# CruiseControlSystemElectricalSchematic_1.net
KiCad netlist of a schematic drawn in EasyEDA
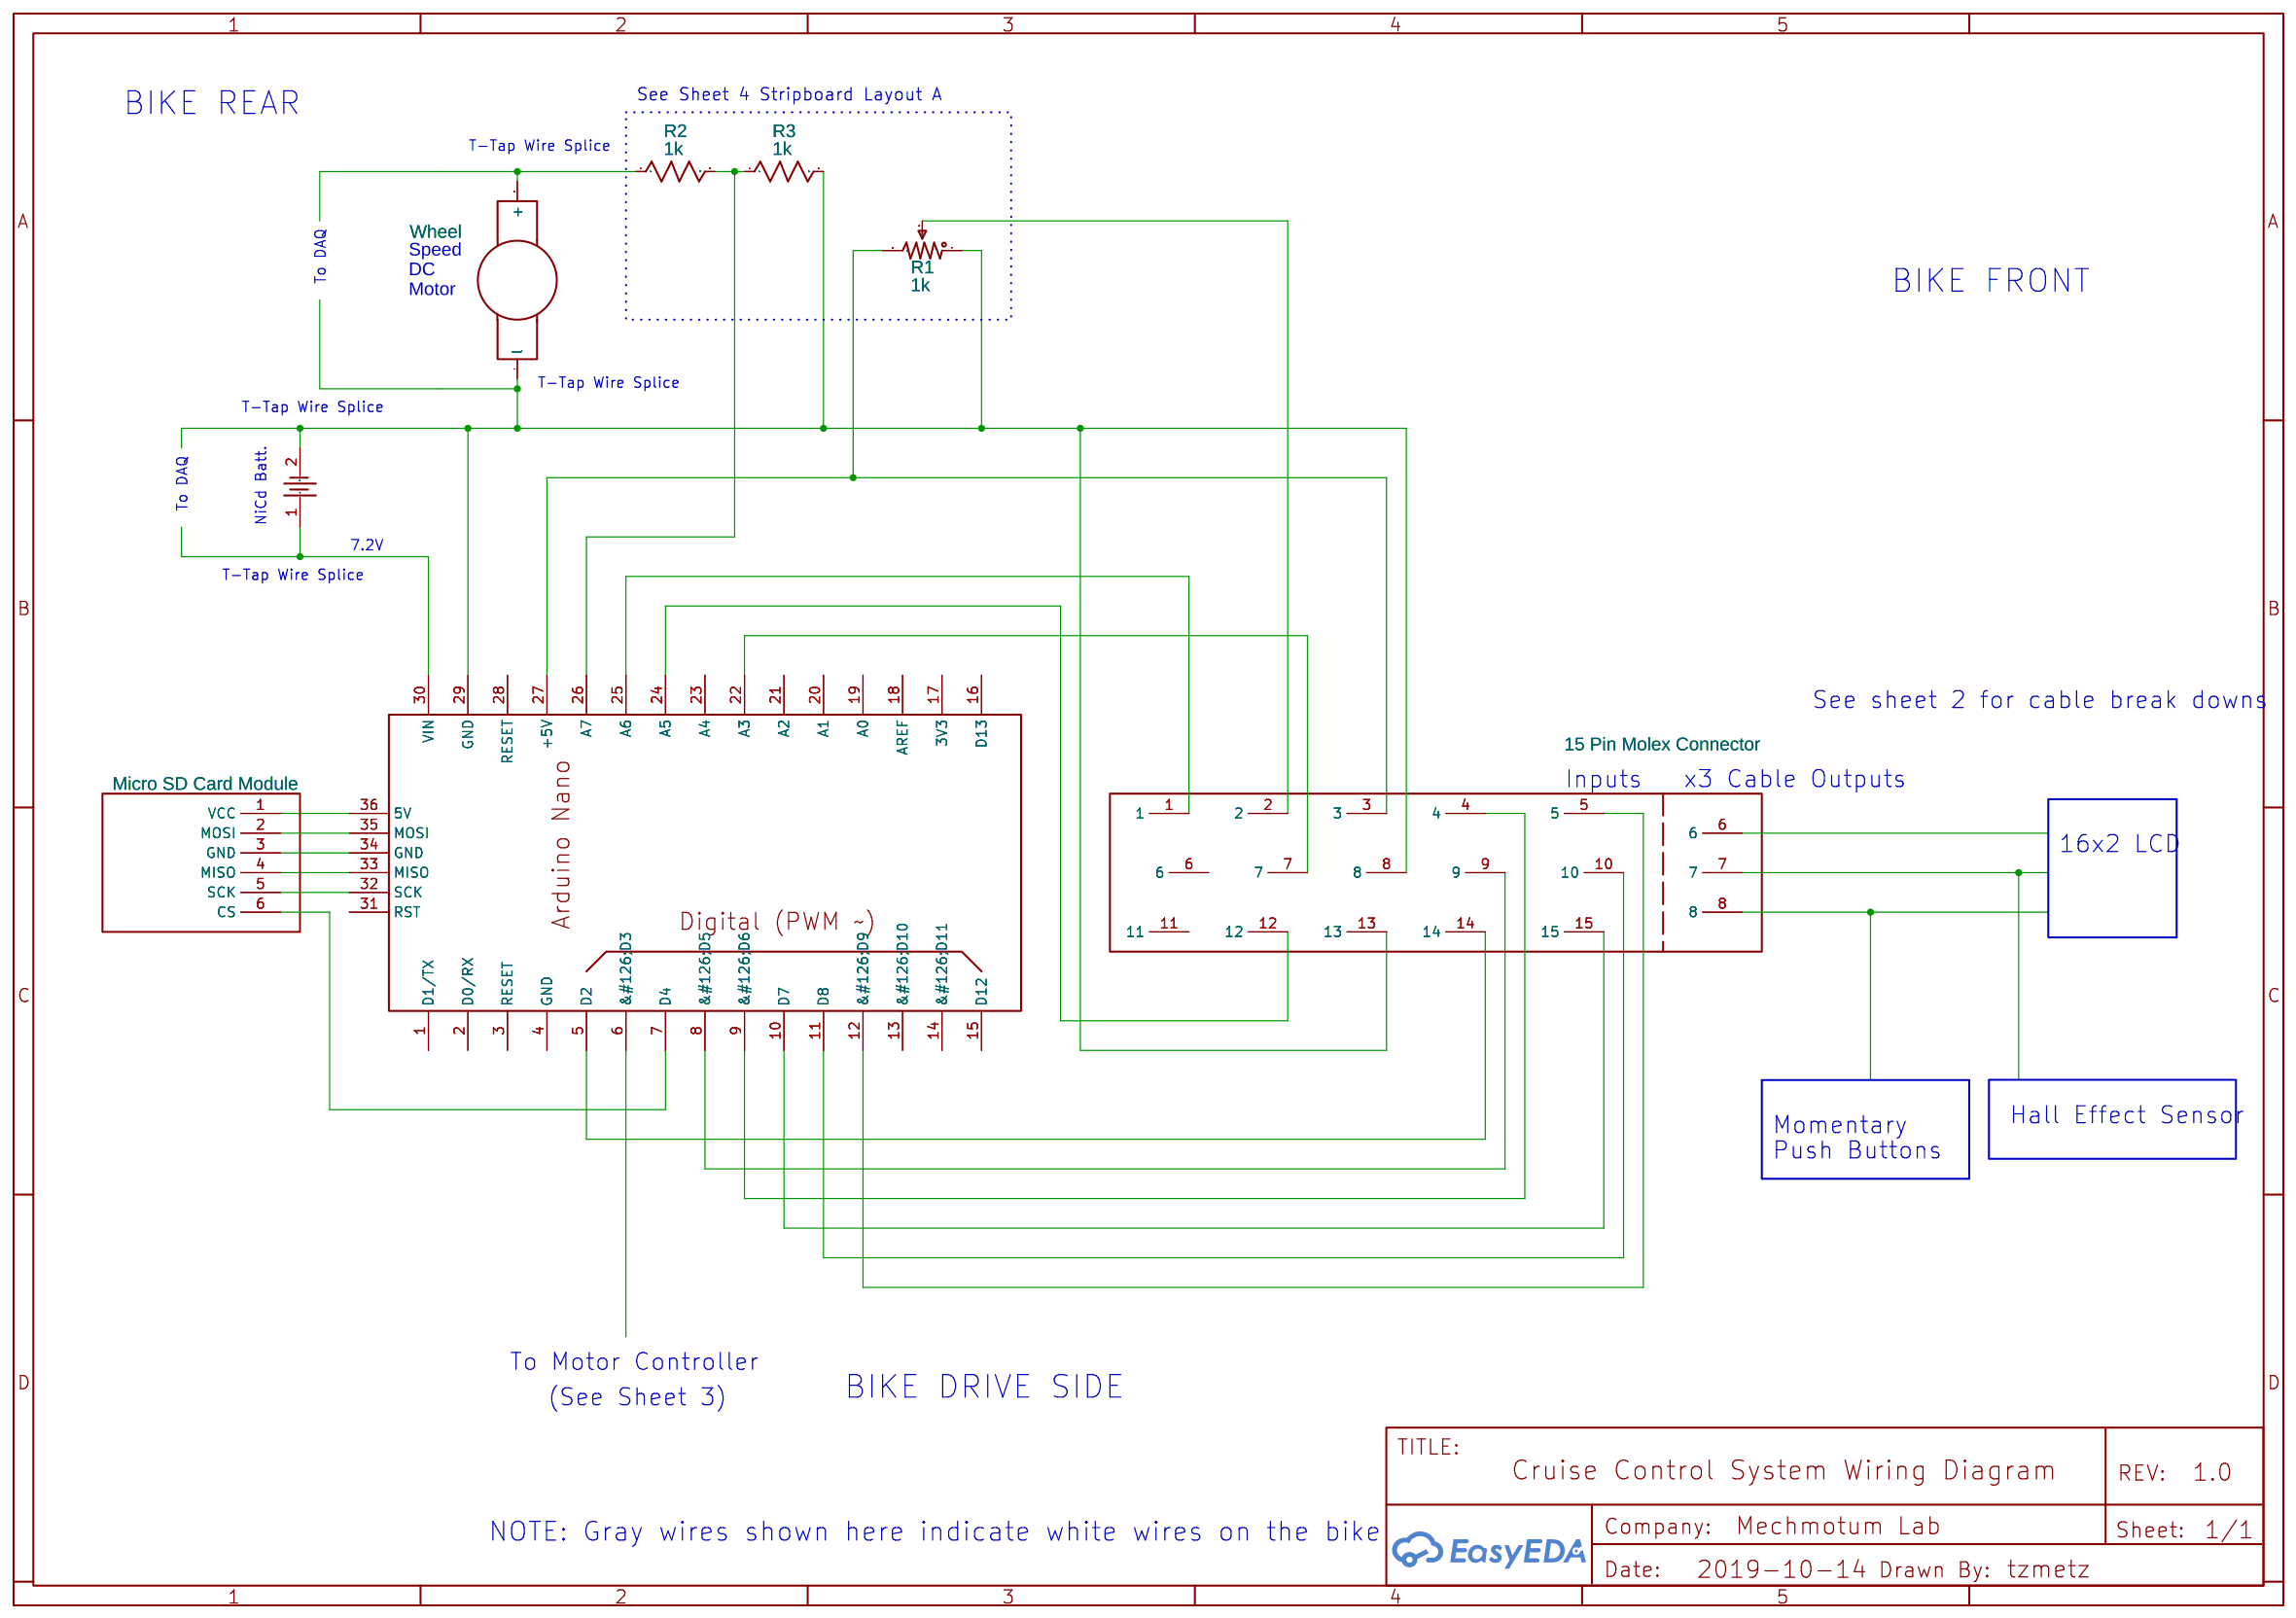
[diagram p0: Sheet_1]
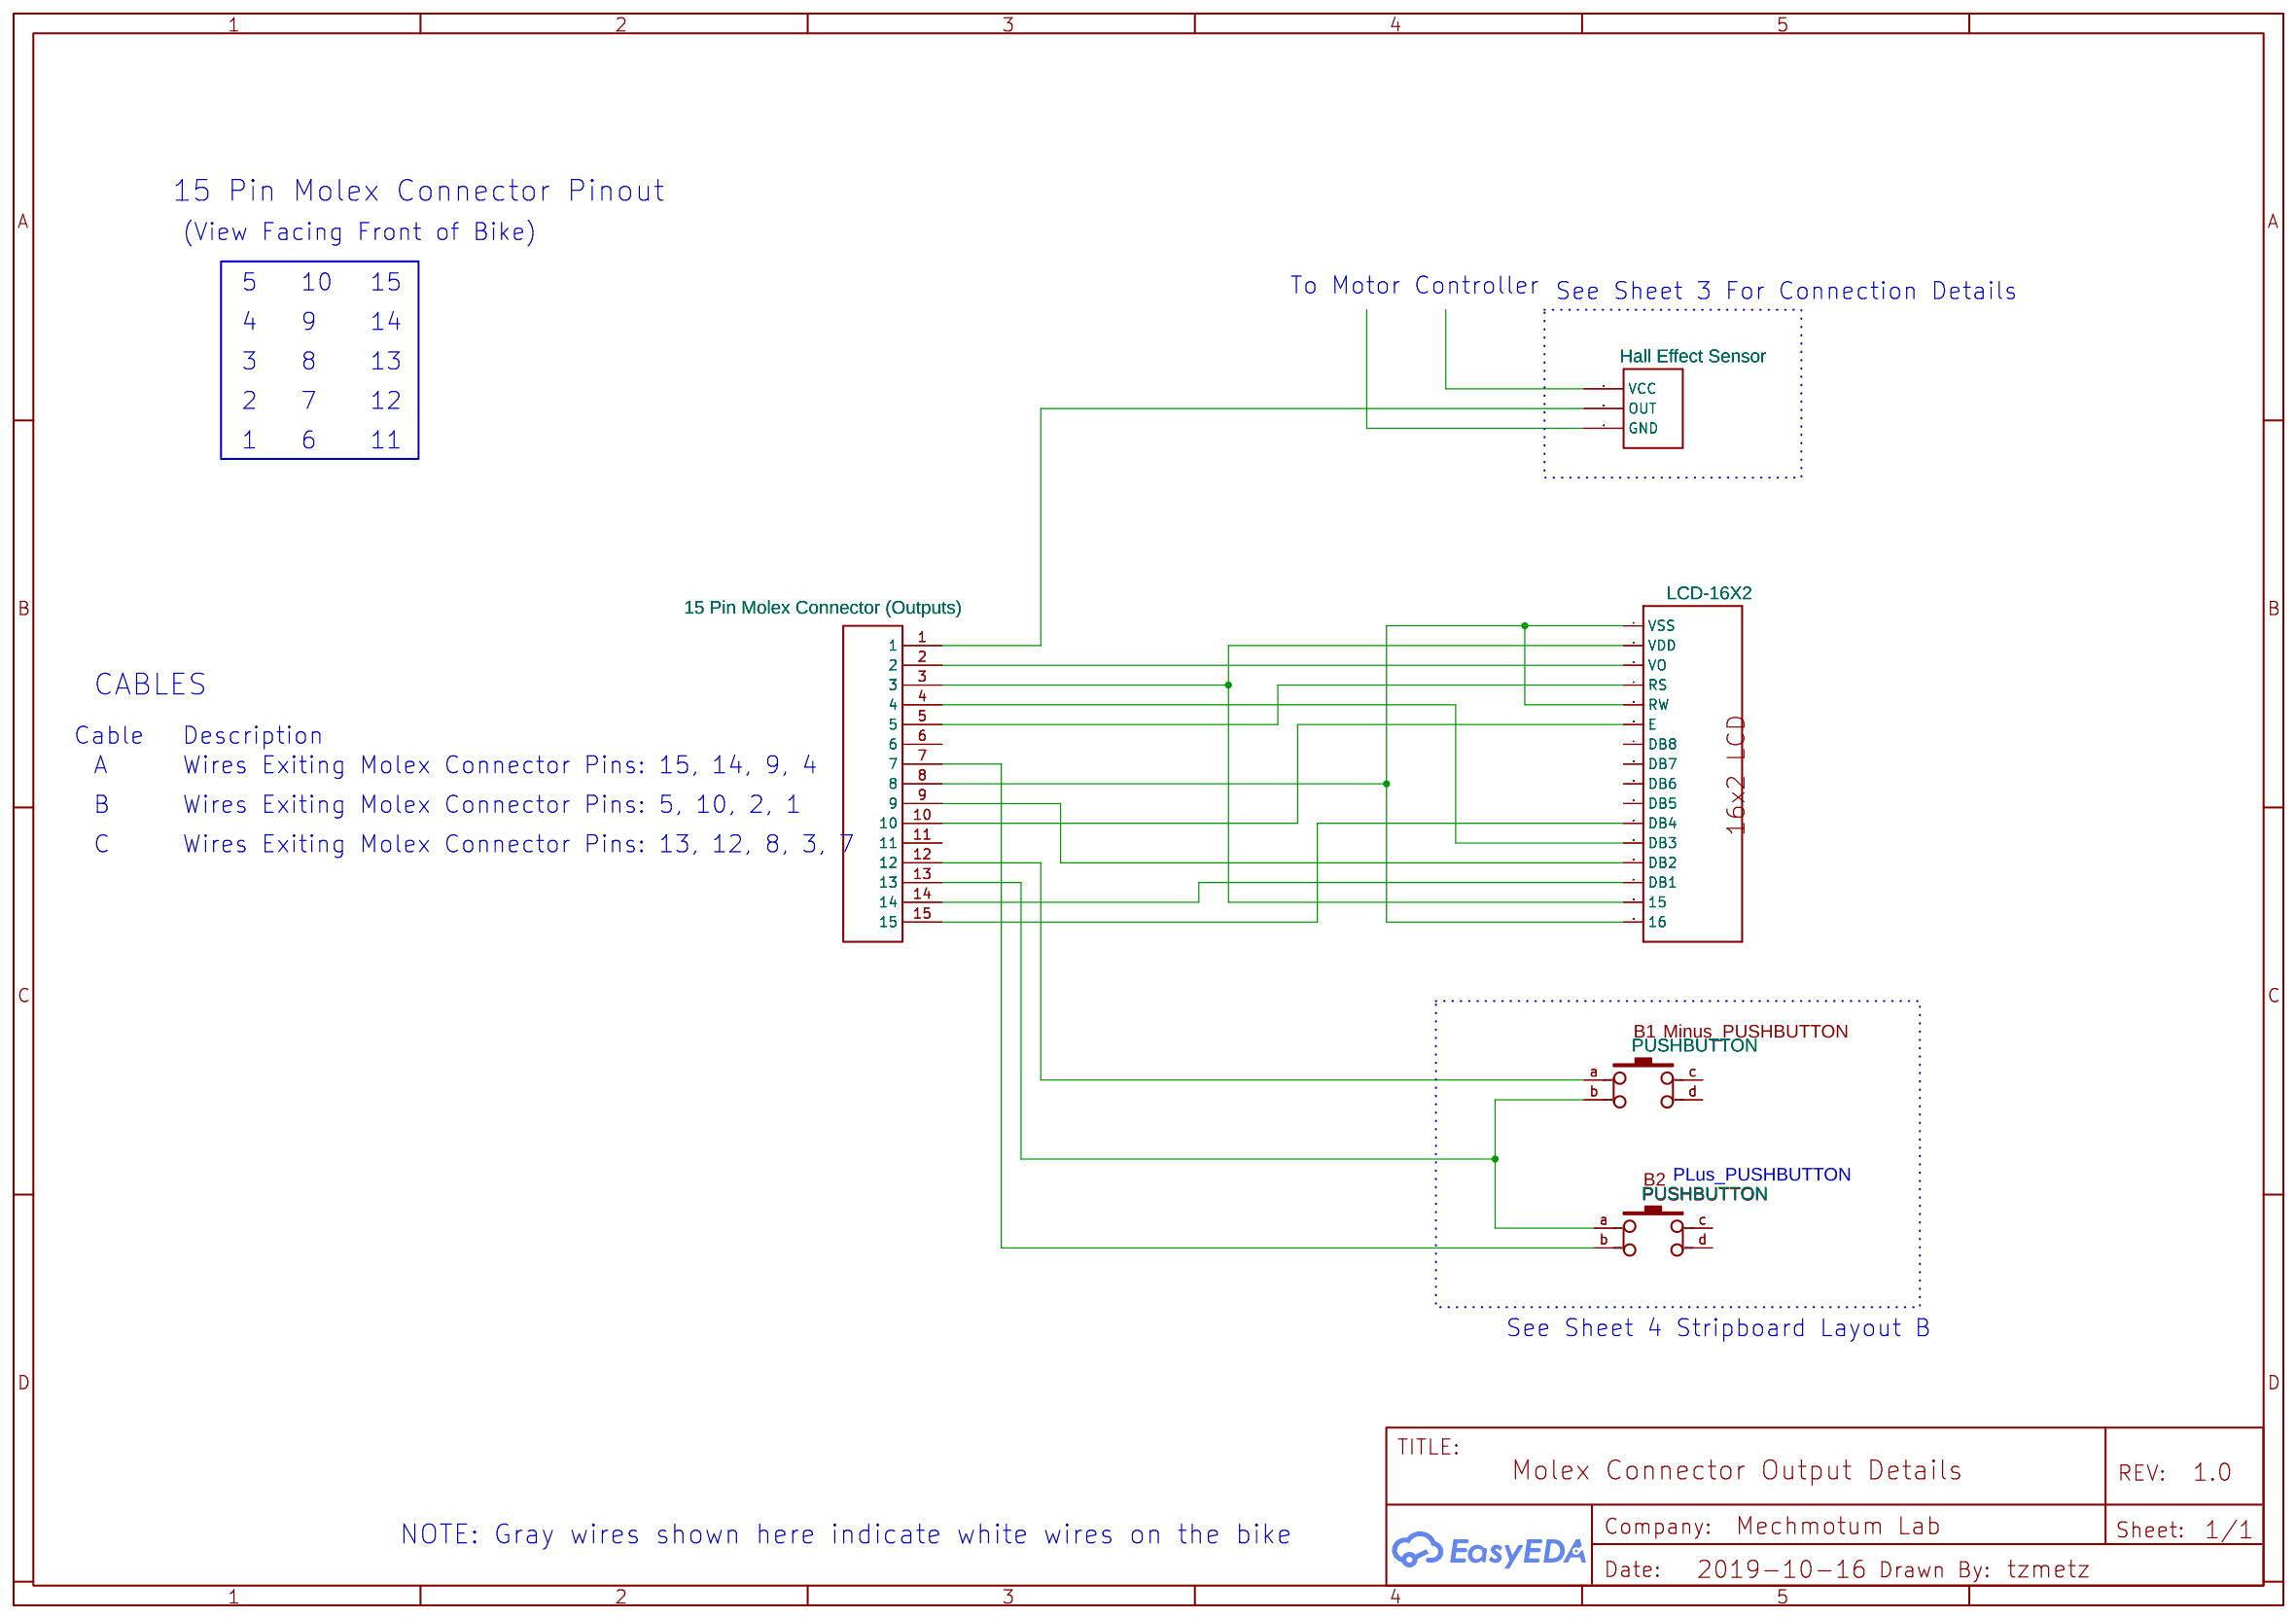
[diagram p1: Sheet_2]
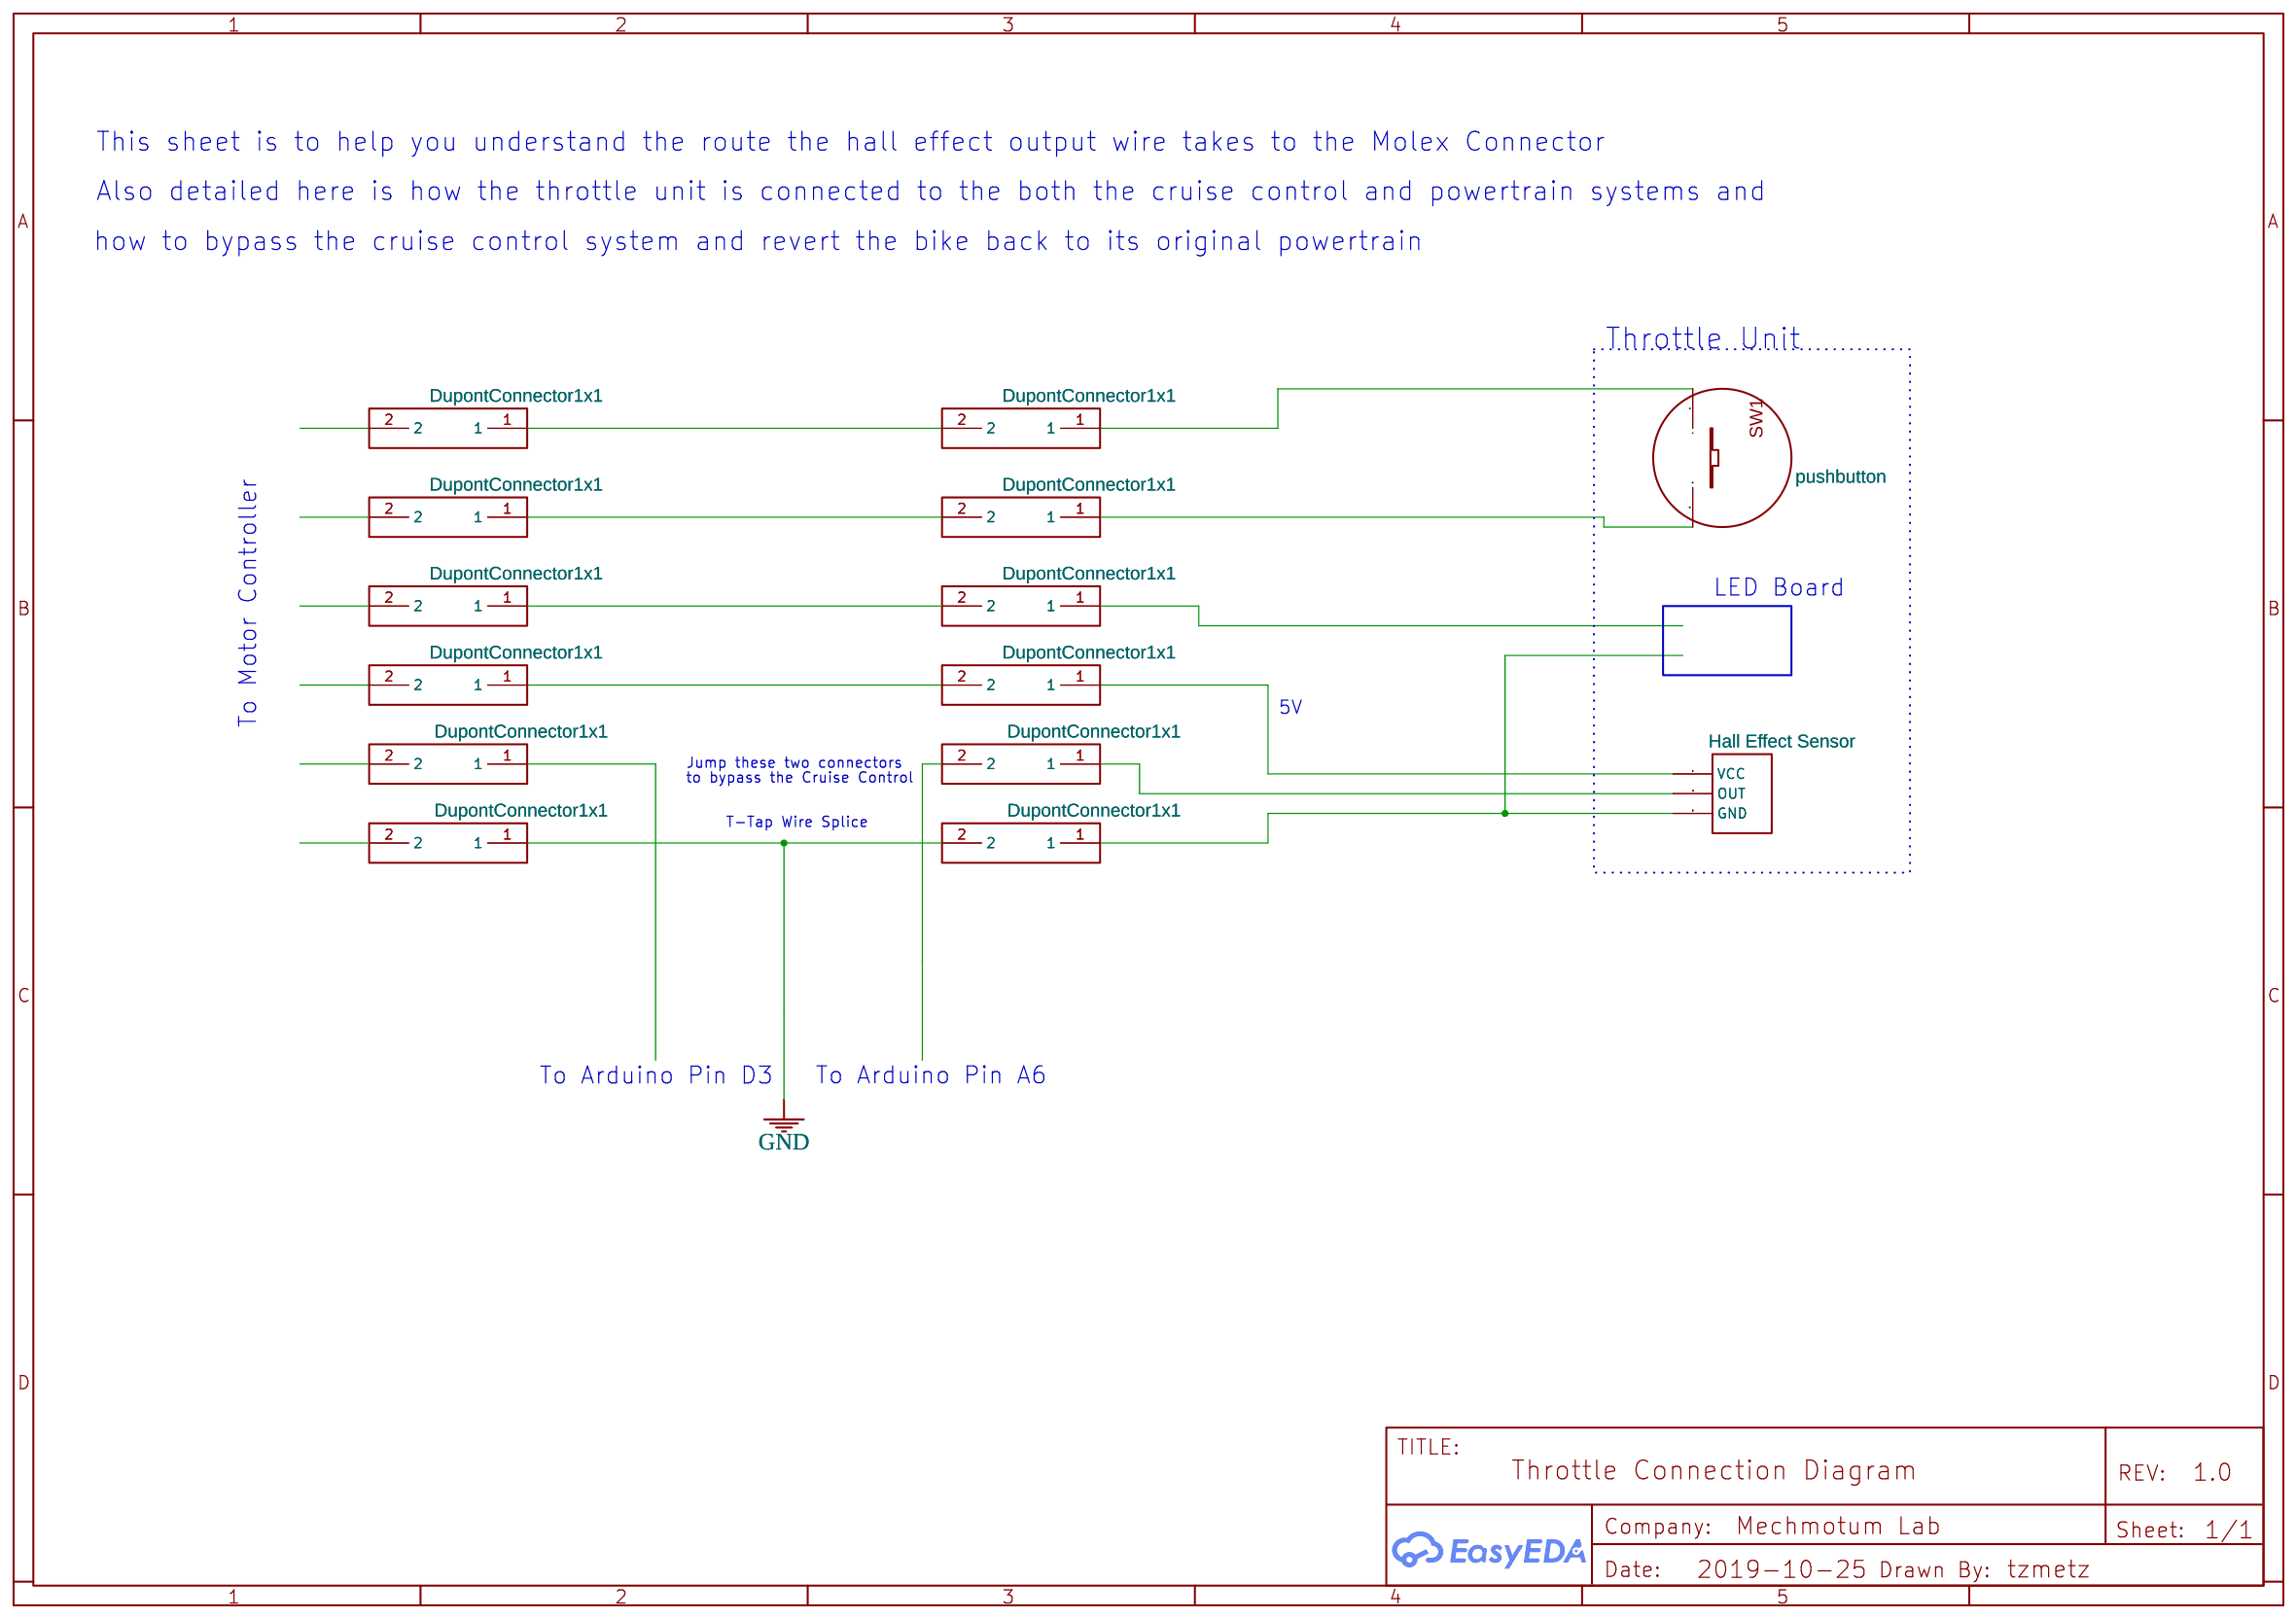
[diagram p2: Sheet_3]
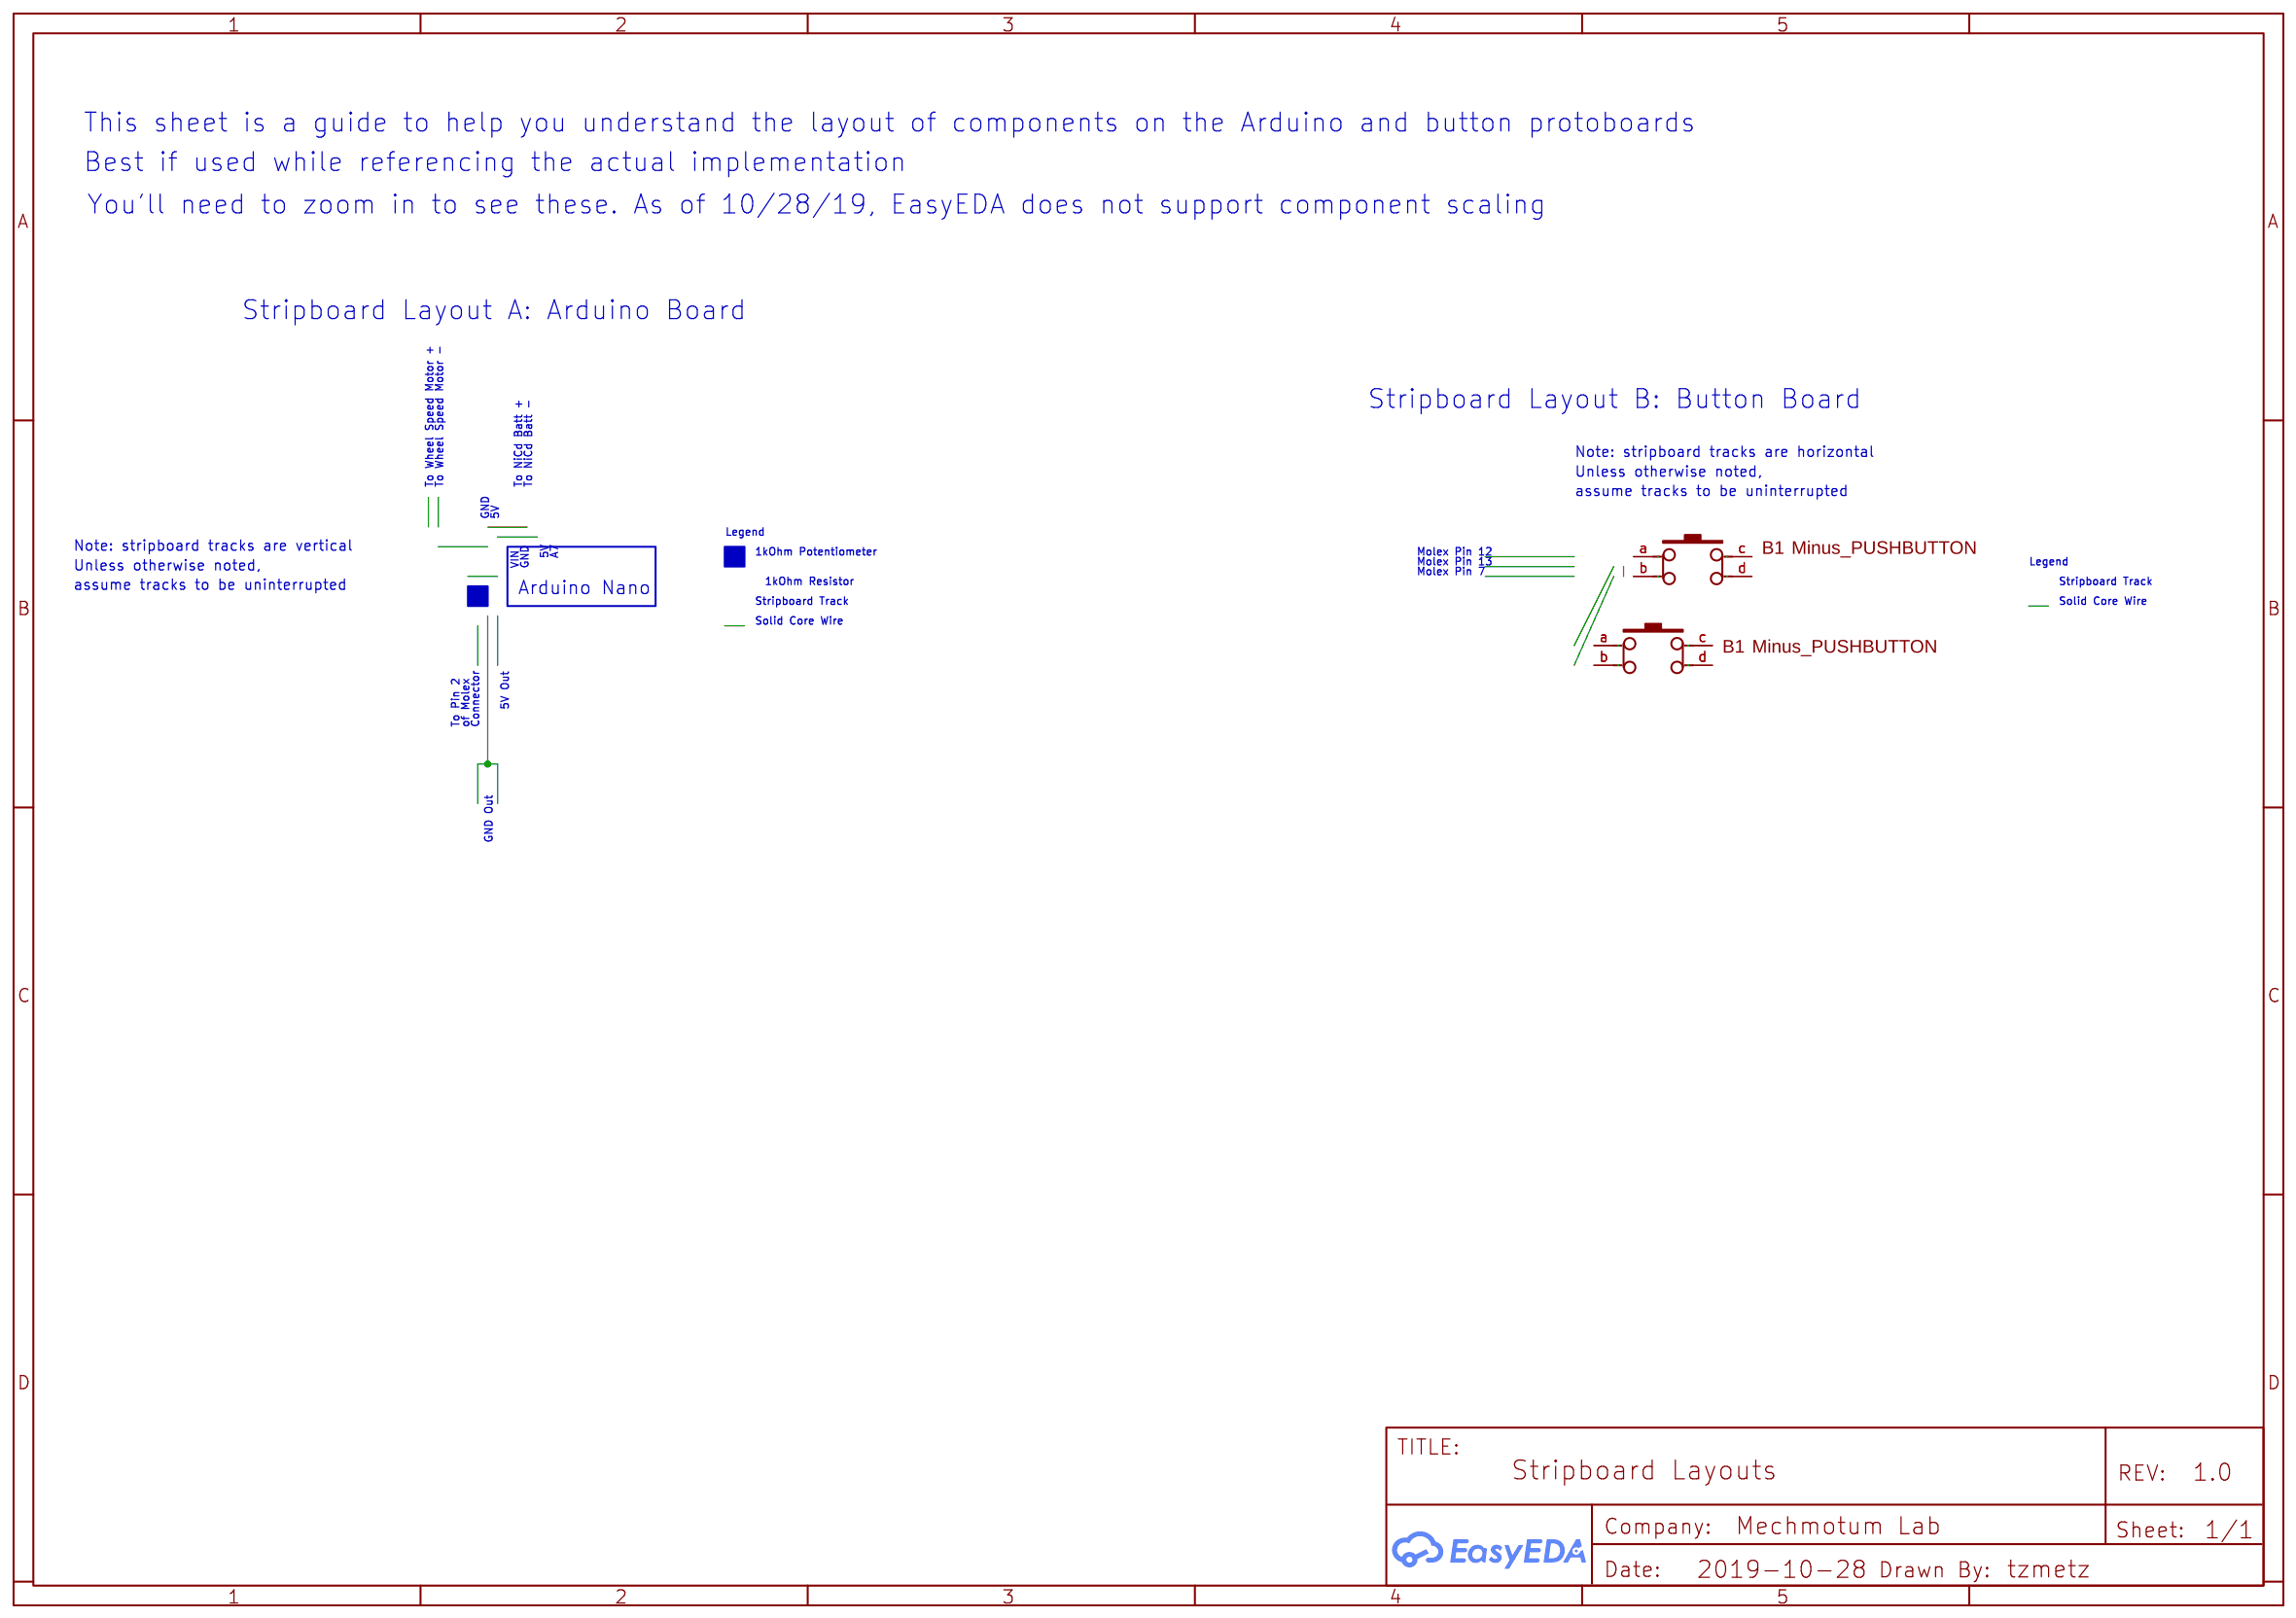
[diagram p3: Sheet_4]
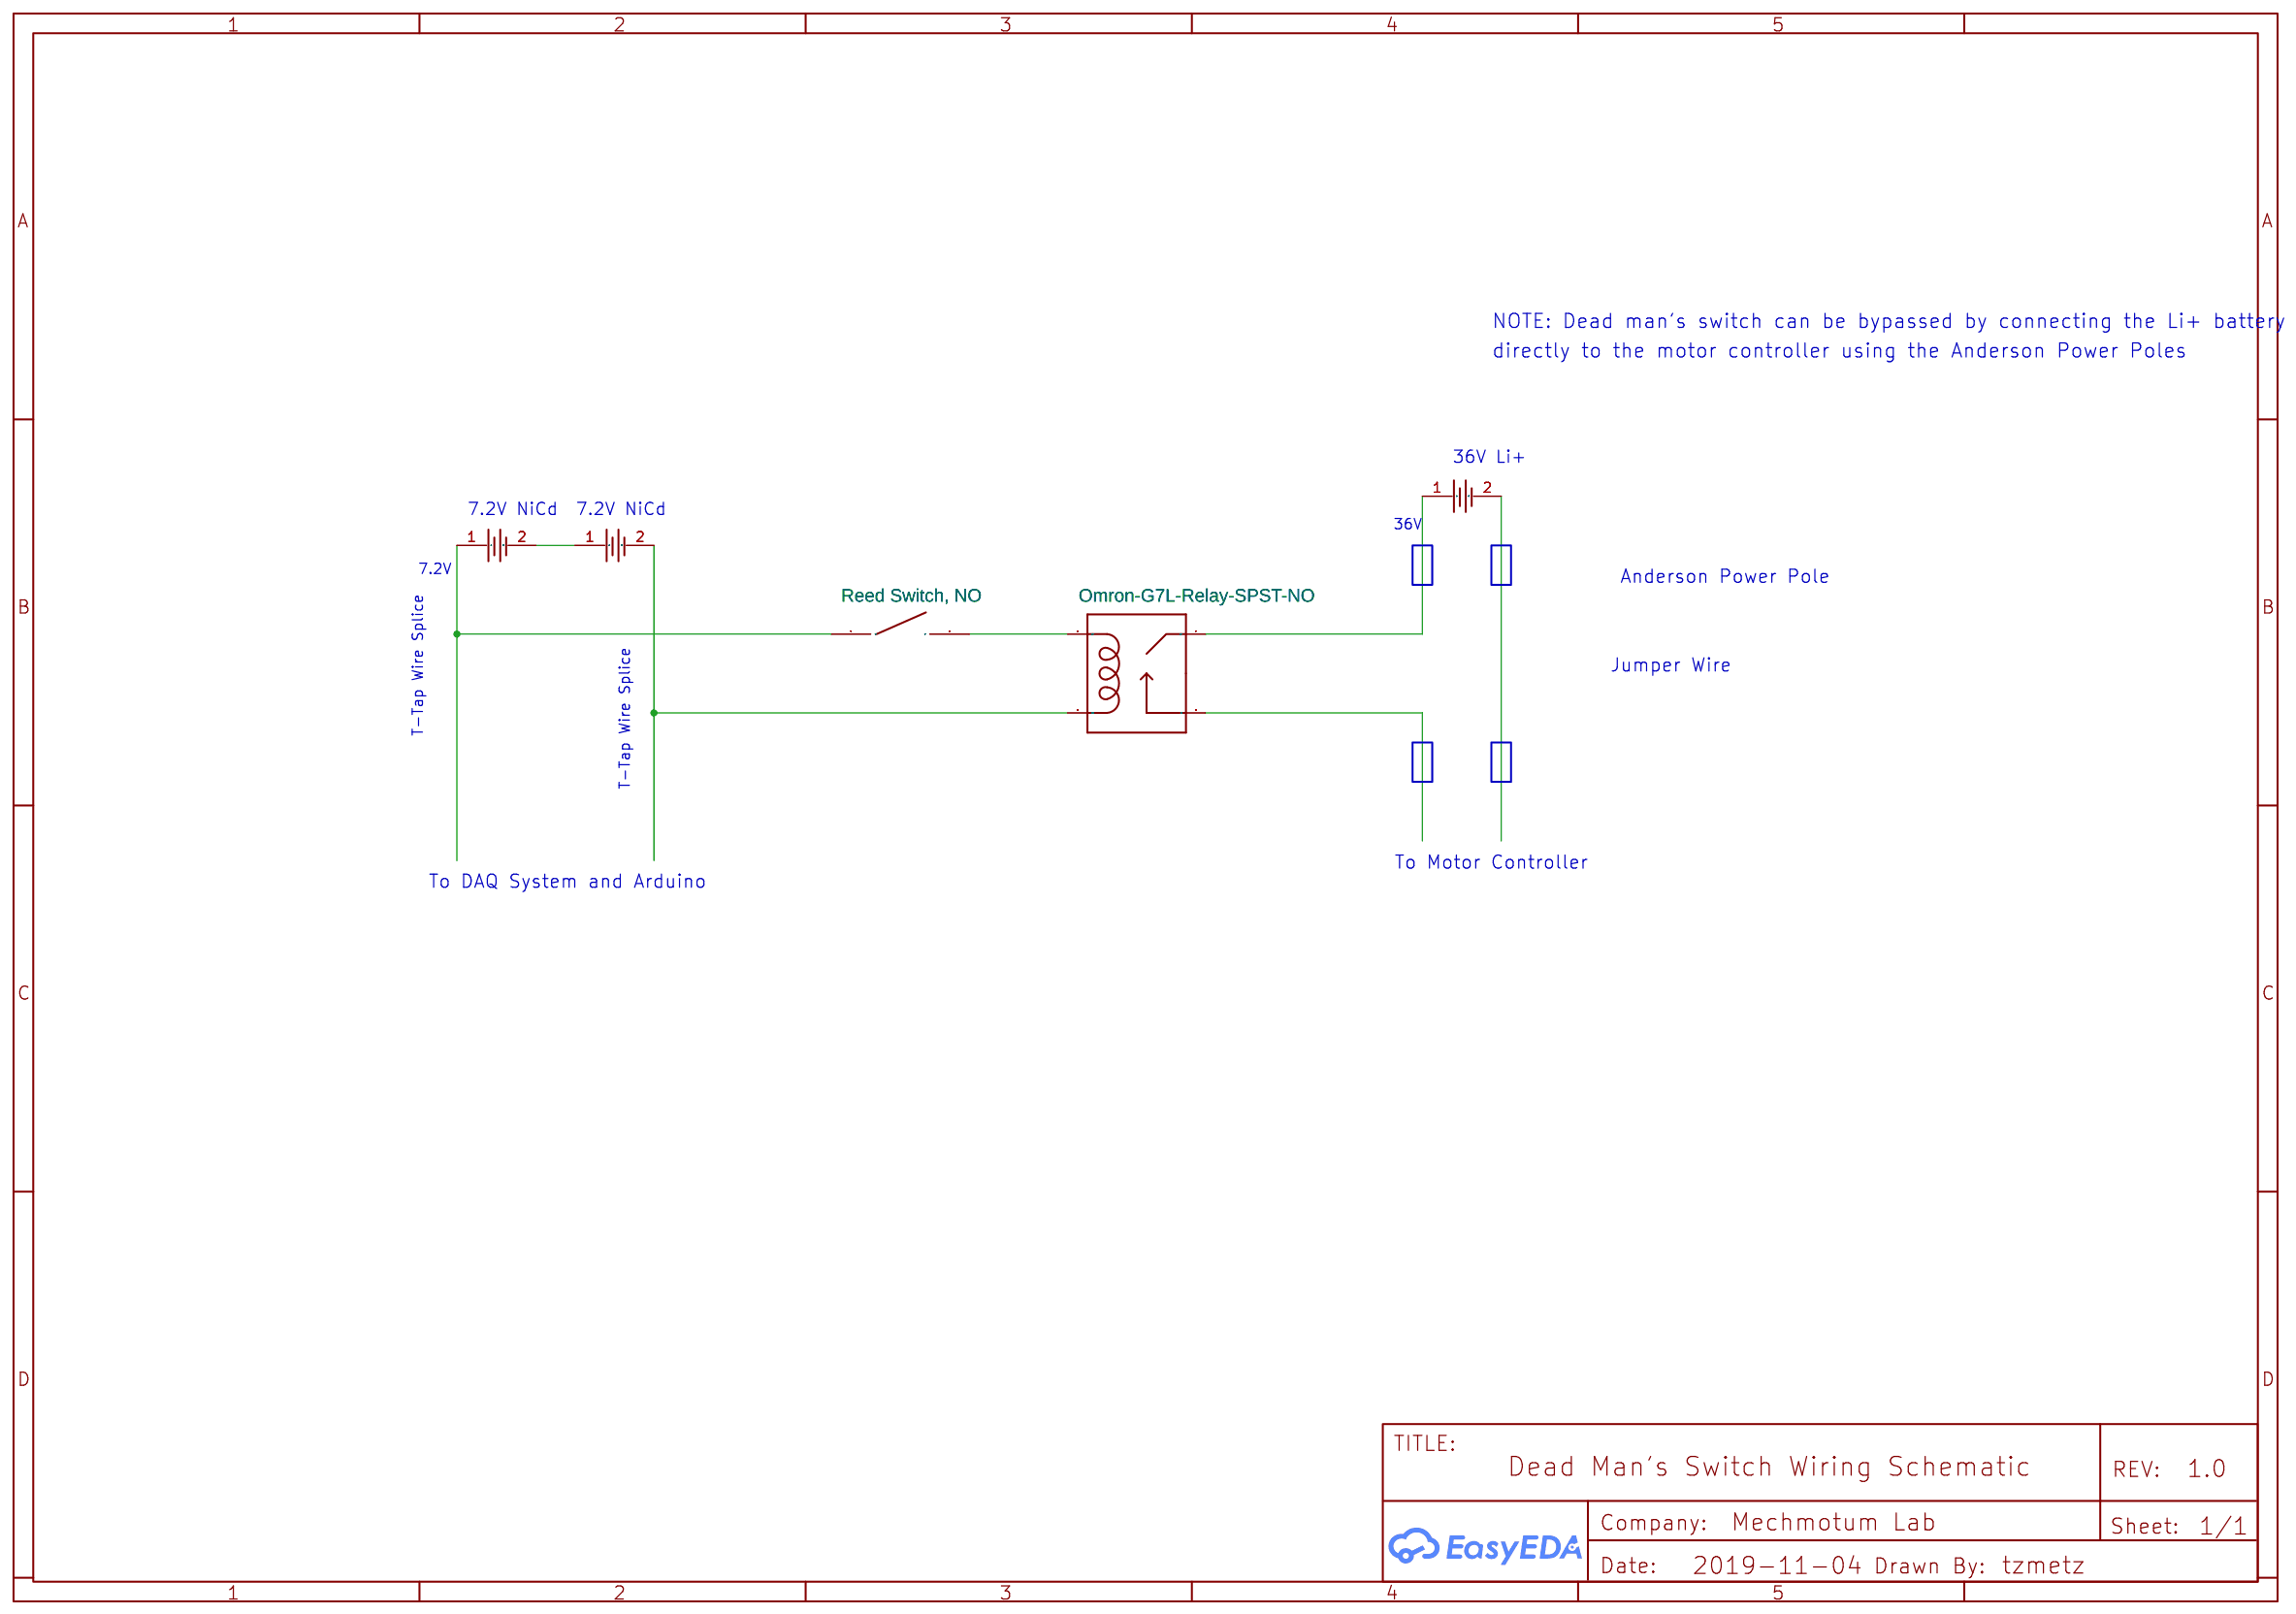
[diagram p4: Sheet_5]

(export (version "E")
  (design (tool "Eeschema 10.0.6"))
  (components
    (comp (ref "B1")
      (value "NiCd Battery 7.2V Line")
      (fields (field (name "BOM_Manufacturer Part") "BS-2-1") (field (name "BOM_Supplier Part") "C70376"))
      (libsource (lib "") (part "Unknown_145_240"))
    )
    (comp (ref "R1")
      (value "1k")
      (fields
        (field (name "BOM_Manufacturer Part") "3386P-1-101LF")
        (field (name "BOM_Supplier Part") "C125022")
      )
      (libsource (lib "") (part "3386P-1-101LF_US"))
    )
    (comp (ref "R2") (value "1k") (libsource (lib "") (part "Res_AXIAL-0.3(1/8W)_US")))
    (comp (ref "R3") (value "1k") (libsource (lib "") (part "Res_AXIAL-0.3(1/8W)_US")))
    (comp (ref "U2")
      (value "ARDUINO_NANO COPY")
      (fields (field (name "BOM_Manufacturer Part") "ARDUINO_NANO_LIVETHINGS"))
      (libsource (lib "") (part "Unknown_350_425"))
    )
    (comp (ref "U5") (value "Wheel") (libsource (lib "") (part "Unknown_255_135")))
    (comp (ref "U8") (value "Micro SD Card Module") (libsource (lib "") (part "Unknown_105_425")))
    (comp (ref "U10") (value "15 Pin Molex Connector") (libsource (lib "") (part "Unknown_635_435")))
    (comp (ref "U1") (value "PUSHBUTTON") (libsource (lib "") (part "Unknown_860_635")))
    (comp (ref "U6") (value "15 Pin Molex Connector (Outputs)") (libsource (lib "") (part "Unknown_450_310")))
    (comp (ref "U11") (value "LCD-16X2") (libsource (lib "") (part "Unknown_845_385")))
    (comp (ref "U12") (value "PUSHBUTTON") (libsource (lib "") (part "Unknown_855_560")))
    (comp (ref "U13") (value "Hall Effect Sensor") (libsource (lib "") (part "Unknown_795_180")))
    (comp (ref "U3")
      (value "pushbutton")
      (fields (field (name "BOM_Manufacturer Part") "push button"))
      (libsource (lib "") (part "Unknown_875_220"))
    )
    (comp (ref "U4") (value "Hall Effect Sensor") (libsource (lib "") (part "Unknown_840_375")))
    (comp (ref "U7") (value "DupontConnector1x1") (libsource (lib "") (part "Unknown_510_380")))
    (comp (ref "U9") (value "DupontConnector1x1") (libsource (lib "") (part "Unknown_510_420")))
    (comp (ref "U14") (value "DupontConnector1x1") (libsource (lib "") (part "Unknown_510_300")))
    (comp (ref "U15") (value "DupontConnector1x1") (libsource (lib "") (part "Unknown_510_340")))
    (comp (ref "U16") (value "DupontConnector1x1") (libsource (lib "") (part "Unknown_510_255")))
    (comp (ref "U17") (value "DupontConnector1x1") (libsource (lib "") (part "Unknown_510_210")))
    (comp (ref "U18") (value "DupontConnector1x1") (libsource (lib "") (part "Unknown_220_210")))
    (comp (ref "U19") (value "DupontConnector1x1") (libsource (lib "") (part "Unknown_220_255")))
    (comp (ref "U20") (value "DupontConnector1x1") (libsource (lib "") (part "Unknown_220_340")))
    (comp (ref "U21") (value "DupontConnector1x1") (libsource (lib "") (part "Unknown_220_300")))
    (comp (ref "U22") (value "DupontConnector1x1") (libsource (lib "") (part "Unknown_220_420")))
    (comp (ref "U23") (value "DupontConnector1x1") (libsource (lib "") (part "Unknown_220_380")))
    (comp (ref "U24") (value "PUSHBUTTON") (libsource (lib "") (part "Unknown_880_295")))
    (comp (ref "U25") (value "PUSHBUTTON") (libsource (lib "") (part "Unknown_860_340")))
    (comp (ref "B2")
      (value "BS-2-1")
      (fields (field (name "BOM_Supplier Part") "C70376"))
      (libsource (lib "") (part "Unknown_245_270"))
    )
    (comp (ref "B3")
      (value "BS-2-1")
      (fields (field (name "BOM_Supplier Part") "C70376"))
      (libsource (lib "") (part "Unknown_305_270"))
    )
    (comp (ref "B4")
      (value "BS-2-1")
      (fields (field (name "BOM_Supplier Part") "C70376"))
      (libsource (lib "") (part "Unknown_735_245"))
    )
    (comp (ref "RL1") (value "Omron-G7L-Relay-SPST-NO") (libsource (lib "") (part "Unknown_575_335")))
    (comp (ref "SW1")
      (value "Reed Switch, NO")
      (fields (field (name "BOM_Manufacturer Part") "EVQ22705R") (field (name "BOM_Supplier Part") "C79156"))
      (libsource (lib "") (part "Unknown_450_315"))
    )
  )
  (nets
    (net (code "1") (name "GND") (class "Default")
      (node (ref "U22") (pin "1") (pinfunction "1_1") (pintype "unspecified"))
      (node (ref "U9") (pin "2") (pinfunction "2_2") (pintype "unspecified"))
    )
    (net (code "2") (name "Net-(B2-Pad1)") (class "Default")
      (node (ref "B2") (pin "1") (pinfunction "1_1") (pintype "input"))
      (node (ref "SW1") (pin "1") (pinfunction "1_1") (pintype "input"))
    )
    (net (code "3") (name "Net-(B2-Pad2)") (class "Default")
      (node (ref "B2") (pin "2") (pinfunction "2_2") (pintype "input"))
      (node (ref "B3") (pin "1") (pinfunction "1_1") (pintype "input"))
    )
    (net (code "4") (name "Net-(R1-Pad2)") (class "Default")
      (node (ref "R1") (pin "2") (pinfunction "2_2") (pintype "unspecified"))
      (node (ref "U10") (pin "2") (pinfunction "2_2") (pintype "unspecified"))
    )
    (net (code "5") (name "Net-(RL1-COIL1)") (class "Default")
      (node (ref "B3") (pin "2") (pinfunction "2_2") (pintype "input"))
      (node (ref "RL1") (pin "5") (pinfunction "COIL1_5") (pintype "unspecified"))
    )
    (net (code "6") (name "Net-(RL1-COIL2)") (class "Default")
      (node (ref "RL1") (pin "2") (pinfunction "COIL2_2") (pintype "unspecified"))
      (node (ref "SW1") (pin "2") (pinfunction "2_2") (pintype "input"))
    )
    (net (code "7") (name "Net-(RL1-MAIN)") (class "Default")
      (node (ref "B4") (pin "1") (pinfunction "1_1") (pintype "input"))
      (node (ref "RL1") (pin "1") (pinfunction "MAIN_1") (pintype "unspecified"))
    )
    (net (code "8") (name "Net-(U1-1-Pada)") (class "Default")
      (node (ref "U1") (pin "a") (pinfunction "1_a") (pintype "input"))
      (node (ref "U12") (pin "b") (pinfunction "1_b") (pintype "input"))
      (node (ref "U6") (pin "13") (pinfunction "13_13") (pintype "unspecified"))
    )
    (net (code "9") (name "Net-(U1-1-Padb)") (class "Default")
      (node (ref "U1") (pin "b") (pinfunction "1_b") (pintype "input"))
      (node (ref "U6") (pin "7") (pinfunction "7_7") (pintype "unspecified"))
    )
    (net (code "10") (name "Net-(U2-&#126;D5)") (class "Default")
      (node (ref "U10") (pin "9") (pinfunction "9_9") (pintype "unspecified"))
      (node (ref "U2") (pin "8") (pinfunction "&#126;D5_8") (pintype "unspecified"))
    )
    (net (code "11") (name "Net-(U2-&#126;D6)") (class "Default")
      (node (ref "U10") (pin "4") (pinfunction "4_4") (pintype "unspecified"))
      (node (ref "U2") (pin "9") (pinfunction "&#126;D6_9") (pintype "unspecified"))
    )
    (net (code "12") (name "Net-(U2-&#126;D9)") (class "Default")
      (node (ref "U10") (pin "5") (pinfunction "5_5") (pintype "unspecified"))
      (node (ref "U2") (pin "12") (pinfunction "&#126;D9_12") (pintype "unspecified"))
    )
    (net (code "13") (name "Net-(U2-+5V)") (class "Default")
      (node (ref "R1") (pin "3") (pinfunction "3_3") (pintype "unspecified"))
      (node (ref "U10") (pin "3") (pinfunction "3_3") (pintype "unspecified"))
      (node (ref "U2") (pin "27") (pinfunction "+5V_27") (pintype "unspecified"))
    )
    (net (code "14") (name "Net-(U2-5V)") (class "Default")
      (node (ref "U2") (pin "36") (pinfunction "5V_36") (pintype "unspecified"))
      (node (ref "U8") (pin "1") (pinfunction "VCC_1") (pintype "unspecified"))
    )
    (net (code "15") (name "Net-(U2-A3)") (class "Default")
      (node (ref "U10") (pin "7") (pinfunction "7_7") (pintype "unspecified"))
      (node (ref "U2") (pin "22") (pinfunction "A3_22") (pintype "unspecified"))
    )
    (net (code "16") (name "Net-(U2-A5)") (class "Default")
      (node (ref "U10") (pin "12") (pinfunction "12_12") (pintype "unspecified"))
      (node (ref "U2") (pin "24") (pinfunction "A5_24") (pintype "unspecified"))
    )
    (net (code "17") (name "Net-(U2-A6)") (class "Default")
      (node (ref "U10") (pin "1") (pinfunction "1_1") (pintype "unspecified"))
      (node (ref "U2") (pin "25") (pinfunction "A6_25") (pintype "unspecified"))
    )
    (net (code "18") (name "Net-(U2-A7)") (class "Default")
      (node (ref "R2") (pin "2") (pinfunction "2_2") (pintype "unspecified"))
      (node (ref "R3") (pin "1") (pinfunction "1_1") (pintype "unspecified"))
      (node (ref "U2") (pin "26") (pinfunction "A7_26") (pintype "unspecified"))
    )
    (net (code "19") (name "Net-(U2-D2)") (class "Default")
      (node (ref "U10") (pin "14") (pinfunction "14_14") (pintype "unspecified"))
      (node (ref "U2") (pin "5") (pinfunction "D2_5") (pintype "unspecified"))
    )
    (net (code "20") (name "Net-(U2-D4)") (class "Default")
      (node (ref "U2") (pin "7") (pinfunction "D4_7") (pintype "unspecified"))
      (node (ref "U8") (pin "6") (pinfunction "CS_6") (pintype "unspecified"))
    )
    (net (code "21") (name "Net-(U2-D7)") (class "Default")
      (node (ref "U10") (pin "15") (pinfunction "15_15") (pintype "unspecified"))
      (node (ref "U2") (pin "10") (pinfunction "D7_10") (pintype "unspecified"))
    )
    (net (code "22") (name "Net-(U2-D8)") (class "Default")
      (node (ref "U10") (pin "10") (pinfunction "10_10") (pintype "unspecified"))
      (node (ref "U2") (pin "11") (pinfunction "D8_11") (pintype "unspecified"))
    )
    (net (code "23") (name "Net-(U2-MISO)") (class "Default")
      (node (ref "U2") (pin "33") (pinfunction "MISO_33") (pintype "unspecified"))
      (node (ref "U8") (pin "4") (pinfunction "MISO_4") (pintype "unspecified"))
    )
    (net (code "24") (name "Net-(U2-MOSI)") (class "Default")
      (node (ref "U2") (pin "35") (pinfunction "MOSI_35") (pintype "unspecified"))
      (node (ref "U8") (pin "2") (pinfunction "MOSI_2") (pintype "unspecified"))
    )
    (net (code "25") (name "Net-(U2-SCK)") (class "Default")
      (node (ref "U2") (pin "32") (pinfunction "SCK_32") (pintype "unspecified"))
      (node (ref "U8") (pin "5") (pinfunction "SCK_5") (pintype "unspecified"))
    )
    (net (code "26") (name "Net-(U2-VIN)") (class "Default")
      (node (ref "B1") (pin "1") (pinfunction "1_1") (pintype "input"))
      (node (ref "U2") (pin "30") (pinfunction "VIN_30") (pintype "unspecified"))
    )
    (net (code "27") (name "Net-(U4-GND)") (class "Default")
      (node (ref "U4") (pin "3") (pinfunction "GND_3") (pintype "unspecified"))
      (node (ref "U9") (pin "1") (pinfunction "1_1") (pintype "unspecified"))
    )
    (net (code "28") (name "Net-(U4-OUT)") (class "Default")
      (node (ref "U4") (pin "2") (pinfunction "OUT_2") (pintype "unspecified"))
      (node (ref "U7") (pin "1") (pinfunction "1_1") (pintype "unspecified"))
    )
    (net (code "29") (name "Net-(U4-VCC)") (class "Default")
      (node (ref "U15") (pin "1") (pinfunction "1_1") (pintype "unspecified"))
      (node (ref "U4") (pin "1") (pinfunction "VCC_1") (pintype "unspecified"))
    )
    (net (code "30") (name "Net-(U5-+)") (class "Default")
      (node (ref "R2") (pin "1") (pinfunction "1_1") (pintype "unspecified"))
      (node (ref "U5") (pin "1") (pinfunction "+_1") (pintype "unspecified"))
    )
    (net (code "31") (name "Net-(U5-l)") (class "Default")
      (node (ref "B1") (pin "2") (pinfunction "2_2") (pintype "input"))
      (node (ref "R1") (pin "1") (pinfunction "1_1") (pintype "unspecified"))
      (node (ref "R3") (pin "2") (pinfunction "2_2") (pintype "unspecified"))
      (node (ref "U10") (pin "13") (pinfunction "13_13") (pintype "unspecified"))
      (node (ref "U10") (pin "8") (pinfunction "8_8") (pintype "unspecified"))
      (node (ref "U2") (pin "29") (pinfunction "GND_29") (pintype "unspecified"))
      (node (ref "U5") (pin "-") (pinfunction "l_-") (pintype "unspecified"))
    )
    (net (code "32") (name "Net-(U8-GND)") (class "Default")
      (node (ref "U2") (pin "34") (pinfunction "GND_34") (pintype "unspecified"))
      (node (ref "U8") (pin "3") (pinfunction "GND_3") (pintype "unspecified"))
    )
    (net (code "33") (name "Net-(U11-DB1)") (class "Default")
      (node (ref "U11") (pin "14") (pinfunction "DB1_14") (pintype "unspecified"))
      (node (ref "U6") (pin "14") (pinfunction "14_14") (pintype "unspecified"))
    )
    (net (code "34") (name "Net-(U11-DB2)") (class "Default")
      (node (ref "U11") (pin "13") (pinfunction "DB2_13") (pintype "unspecified"))
      (node (ref "U6") (pin "9") (pinfunction "9_9") (pintype "unspecified"))
    )
    (net (code "35") (name "Net-(U11-DB3)") (class "Default")
      (node (ref "U11") (pin "12") (pinfunction "DB3_12") (pintype "unspecified"))
      (node (ref "U6") (pin "4") (pinfunction "4_4") (pintype "unspecified"))
    )
    (net (code "36") (name "Net-(U11-DB4)") (class "Default")
      (node (ref "U11") (pin "11") (pinfunction "DB4_11") (pintype "unspecified"))
      (node (ref "U6") (pin "15") (pinfunction "15_15") (pintype "unspecified"))
    )
    (net (code "37") (name "Net-(U11-E)") (class "Default")
      (node (ref "U11") (pin "6") (pinfunction "E_6") (pintype "input"))
      (node (ref "U6") (pin "10") (pinfunction "10_10") (pintype "unspecified"))
    )
    (net (code "38") (name "Net-(U11-RS)") (class "Default")
      (node (ref "U11") (pin "4") (pinfunction "RS_4") (pintype "input"))
      (node (ref "U6") (pin "5") (pinfunction "5_5") (pintype "unspecified"))
    )
    (net (code "39") (name "Net-(U11-RW)") (class "Default")
      (node (ref "U11") (pin "1") (pinfunction "VSS_1") (pintype "passive"))
      (node (ref "U11") (pin "16") (pinfunction "16_16") (pintype "passive"))
      (node (ref "U11") (pin "5") (pinfunction "RW_5") (pintype "input"))
      (node (ref "U6") (pin "8") (pinfunction "8_8") (pintype "unspecified"))
    )
    (net (code "40") (name "Net-(U11-VDD)") (class "Default")
      (node (ref "U11") (pin "15") (pinfunction "15_15") (pintype "passive"))
      (node (ref "U11") (pin "2") (pinfunction "VDD_2") (pintype "passive"))
      (node (ref "U6") (pin "3") (pinfunction "3_3") (pintype "unspecified"))
    )
    (net (code "41") (name "Net-(U11-VO)") (class "Default")
      (node (ref "U11") (pin "3") (pinfunction "VO_3") (pintype "unspecified"))
      (node (ref "U6") (pin "2") (pinfunction "2_2") (pintype "unspecified"))
    )
    (net (code "42") (name "Net-(U12-1-Pada)") (class "Default")
      (node (ref "U12") (pin "a") (pinfunction "1_a") (pintype "input"))
      (node (ref "U6") (pin "12") (pinfunction "12_12") (pintype "unspecified"))
    )
    (net (code "43") (name "Net-(U13-OUT)") (class "Default")
      (node (ref "U13") (pin "2") (pinfunction "OUT_2") (pintype "unspecified"))
      (node (ref "U6") (pin "1") (pinfunction "1_1") (pintype "unspecified"))
    )
    (net (code "44") (name "Net-(U14-Pad2)") (class "Default")
      (node (ref "U14") (pin "2") (pinfunction "2_2") (pintype "unspecified"))
      (node (ref "U21") (pin "1") (pinfunction "1_1") (pintype "unspecified"))
    )
    (net (code "45") (name "Net-(U15-Pad2)") (class "Default")
      (node (ref "U15") (pin "2") (pinfunction "2_2") (pintype "unspecified"))
      (node (ref "U20") (pin "1") (pinfunction "1_1") (pintype "unspecified"))
    )
    (net (code "46") (name "Net-(U16-Pad1)") (class "Default")
      (node (ref "U16") (pin "1") (pinfunction "1_1") (pintype "unspecified"))
      (node (ref "U3") (pin "2") (pinfunction "2_2") (pintype "input"))
    )
    (net (code "47") (name "Net-(U16-Pad2)") (class "Default")
      (node (ref "U16") (pin "2") (pinfunction "2_2") (pintype "unspecified"))
      (node (ref "U19") (pin "1") (pinfunction "1_1") (pintype "unspecified"))
    )
    (net (code "48") (name "Net-(U17-Pad1)") (class "Default")
      (node (ref "U17") (pin "1") (pinfunction "1_1") (pintype "unspecified"))
      (node (ref "U3") (pin "1") (pinfunction "1_1") (pintype "input"))
    )
    (net (code "49") (name "Net-(U17-Pad2)") (class "Default")
      (node (ref "U17") (pin "2") (pinfunction "2_2") (pintype "unspecified"))
      (node (ref "U18") (pin "1") (pinfunction "1_1") (pintype "unspecified"))
    )
    (net (code "50") (name "unconnected-(B4-Pad2)") (class "Default")
      (node (ref "B4") (pin "2") (pinfunction "2_2") (pintype "input"))
    )
    (net (code "51") (name "unconnected-(RL1-NO-Pad3)") (class "Default")
      (node (ref "RL1") (pin "3") (pinfunction "NO_3") (pintype "unspecified"))
    )
    (net (code "52") (name "unconnected-(U1-2-Padd)") (class "Default")
      (node (ref "U1") (pin "d") (pinfunction "2_d") (pintype "input"))
    )
    (net (code "53") (name "unconnected-(U1-3-Padc)") (class "Default")
      (node (ref "U1") (pin "c") (pinfunction "3_c") (pintype "input"))
    )
    (net (code "54") (name "unconnected-(U2-&#126;D3-Pad6)") (class "Default")
      (node (ref "U2") (pin "6") (pinfunction "&#126;D3_6") (pintype "unspecified"))
    )
    (net (code "55") (name "unconnected-(U2-&#126;D10-Pad13)") (class "Default")
      (node (ref "U2") (pin "13") (pinfunction "&#126;D10_13") (pintype "unspecified"))
    )
    (net (code "56") (name "unconnected-(U2-&#126;D11-Pad14)") (class "Default")
      (node (ref "U2") (pin "14") (pinfunction "&#126;D11_14") (pintype "unspecified"))
    )
    (net (code "57") (name "unconnected-(U2-3V3-Pad17)") (class "Default")
      (node (ref "U2") (pin "17") (pinfunction "3V3_17") (pintype "unspecified"))
    )
    (net (code "58") (name "unconnected-(U2-A0-Pad19)") (class "Default")
      (node (ref "U2") (pin "19") (pinfunction "A0_19") (pintype "unspecified"))
    )
    (net (code "59") (name "unconnected-(U2-A1-Pad20)") (class "Default")
      (node (ref "U2") (pin "20") (pinfunction "A1_20") (pintype "unspecified"))
    )
    (net (code "60") (name "unconnected-(U2-A2-Pad21)") (class "Default")
      (node (ref "U2") (pin "21") (pinfunction "A2_21") (pintype "unspecified"))
    )
    (net (code "61") (name "unconnected-(U2-A4-Pad23)") (class "Default")
      (node (ref "U2") (pin "23") (pinfunction "A4_23") (pintype "unspecified"))
    )
    (net (code "62") (name "unconnected-(U2-AREF-Pad18)") (class "Default")
      (node (ref "U2") (pin "18") (pinfunction "AREF_18") (pintype "unspecified"))
    )
    (net (code "63") (name "unconnected-(U2-D0{slash}RX-Pad2)") (class "Default")
      (node (ref "U2") (pin "2") (pinfunction "D0/RX_2") (pintype "unspecified"))
    )
    (net (code "64") (name "unconnected-(U2-D1{slash}TX-Pad1)") (class "Default")
      (node (ref "U2") (pin "1") (pinfunction "D1/TX_1") (pintype "unspecified"))
    )
    (net (code "65") (name "unconnected-(U2-D12-Pad15)") (class "Default")
      (node (ref "U2") (pin "15") (pinfunction "D12_15") (pintype "unspecified"))
    )
    (net (code "66") (name "unconnected-(U2-D13-Pad16)") (class "Default")
      (node (ref "U2") (pin "16") (pinfunction "D13_16") (pintype "unspecified"))
    )
    (net (code "67") (name "unconnected-(U2-GND-Pad4)") (class "Default")
      (node (ref "U2") (pin "4") (pinfunction "GND_4") (pintype "unspecified"))
    )
    (net (code "68") (name "unconnected-(U2-RESET-Pad3)") (class "Default")
      (node (ref "U2") (pin "3") (pinfunction "RESET_3") (pintype "unspecified"))
    )
    (net (code "69") (name "unconnected-(U2-RESET-Pad28)") (class "Default")
      (node (ref "U2") (pin "28") (pinfunction "RESET_28") (pintype "unspecified"))
    )
    (net (code "70") (name "unconnected-(U2-RST-Pad31)") (class "Default")
      (node (ref "U2") (pin "31") (pinfunction "RST_31") (pintype "unspecified"))
    )
    (net (code "71") (name "unconnected-(U6-Pad6)") (class "Default")
      (node (ref "U6") (pin "6") (pinfunction "6_6") (pintype "unspecified"))
    )
    (net (code "72") (name "unconnected-(U6-Pad11)") (class "Default")
      (node (ref "U6") (pin "11") (pinfunction "11_11") (pintype "unspecified"))
    )
    (net (code "73") (name "unconnected-(U7-Pad2)") (class "Default")
      (node (ref "U7") (pin "2") (pinfunction "2_2") (pintype "unspecified"))
    )
    (net (code "74") (name "unconnected-(U10-Pad6)") (class "Default")
      (node (ref "U10") (pin "6") (pinfunction "6_6") (pintype "unspecified"))
    )
    (net (code "75") (name "unconnected-(U10-Pad6)_1") (class "Default")
      (node (ref "U10") (pin "6") (pinfunction "6_6") (pintype "unspecified"))
    )
    (net (code "76") (name "unconnected-(U10-Pad7)") (class "Default")
      (node (ref "U10") (pin "7") (pinfunction "7_7") (pintype "unspecified"))
    )
    (net (code "77") (name "unconnected-(U10-Pad8)") (class "Default")
      (node (ref "U10") (pin "8") (pinfunction "8_8") (pintype "unspecified"))
    )
    (net (code "78") (name "unconnected-(U10-Pad11)") (class "Default")
      (node (ref "U10") (pin "11") (pinfunction "11_11") (pintype "unspecified"))
    )
    (net (code "79") (name "unconnected-(U11-DB5-Pad10)") (class "Default")
      (node (ref "U11") (pin "10") (pinfunction "DB5_10") (pintype "unspecified"))
    )
    (net (code "80") (name "unconnected-(U11-DB6-Pad9)") (class "Default")
      (node (ref "U11") (pin "9") (pinfunction "DB6_9") (pintype "unspecified"))
    )
    (net (code "81") (name "unconnected-(U11-DB7-Pad8)") (class "Default")
      (node (ref "U11") (pin "8") (pinfunction "DB7_8") (pintype "unspecified"))
    )
    (net (code "82") (name "unconnected-(U11-DB8-Pad7)") (class "Default")
      (node (ref "U11") (pin "7") (pinfunction "DB8_7") (pintype "unspecified"))
    )
    (net (code "83") (name "unconnected-(U12-2-Padd)") (class "Default")
      (node (ref "U12") (pin "d") (pinfunction "2_d") (pintype "input"))
    )
    (net (code "84") (name "unconnected-(U12-3-Padc)") (class "Default")
      (node (ref "U12") (pin "c") (pinfunction "3_c") (pintype "input"))
    )
    (net (code "85") (name "unconnected-(U13-GND-Pad3)") (class "Default")
      (node (ref "U13") (pin "3") (pinfunction "GND_3") (pintype "unspecified"))
    )
    (net (code "86") (name "unconnected-(U13-VCC-Pad1)") (class "Default")
      (node (ref "U13") (pin "1") (pinfunction "VCC_1") (pintype "unspecified"))
    )
    (net (code "87") (name "unconnected-(U14-Pad1)") (class "Default")
      (node (ref "U14") (pin "1") (pinfunction "1_1") (pintype "unspecified"))
    )
    (net (code "88") (name "unconnected-(U18-Pad2)") (class "Default")
      (node (ref "U18") (pin "2") (pinfunction "2_2") (pintype "unspecified"))
    )
    (net (code "89") (name "unconnected-(U19-Pad2)") (class "Default")
      (node (ref "U19") (pin "2") (pinfunction "2_2") (pintype "unspecified"))
    )
    (net (code "90") (name "unconnected-(U20-Pad2)") (class "Default")
      (node (ref "U20") (pin "2") (pinfunction "2_2") (pintype "unspecified"))
    )
    (net (code "91") (name "unconnected-(U21-Pad2)") (class "Default")
      (node (ref "U21") (pin "2") (pinfunction "2_2") (pintype "unspecified"))
    )
    (net (code "92") (name "unconnected-(U22-Pad2)") (class "Default")
      (node (ref "U22") (pin "2") (pinfunction "2_2") (pintype "unspecified"))
    )
    (net (code "93") (name "unconnected-(U23-Pad1)") (class "Default")
      (node (ref "U23") (pin "1") (pinfunction "1_1") (pintype "unspecified"))
    )
    (net (code "94") (name "unconnected-(U23-Pad2)") (class "Default")
      (node (ref "U23") (pin "2") (pinfunction "2_2") (pintype "unspecified"))
    )
    (net (code "95") (name "unconnected-(U24-1-Pada)") (class "Default")
      (node (ref "U24") (pin "a") (pinfunction "1_a") (pintype "input"))
    )
    (net (code "96") (name "unconnected-(U24-1-Padb)") (class "Default")
      (node (ref "U24") (pin "b") (pinfunction "1_b") (pintype "input"))
    )
    (net (code "97") (name "unconnected-(U24-2-Padd)") (class "Default")
      (node (ref "U24") (pin "d") (pinfunction "2_d") (pintype "input"))
    )
    (net (code "98") (name "unconnected-(U24-3-Padc)") (class "Default")
      (node (ref "U24") (pin "c") (pinfunction "3_c") (pintype "input"))
    )
    (net (code "99") (name "unconnected-(U25-1-Pada)") (class "Default")
      (node (ref "U25") (pin "a") (pinfunction "1_a") (pintype "input"))
    )
    (net (code "100") (name "unconnected-(U25-1-Padb)") (class "Default")
      (node (ref "U25") (pin "b") (pinfunction "1_b") (pintype "input"))
    )
    (net (code "101") (name "unconnected-(U25-2-Padd)") (class "Default")
      (node (ref "U25") (pin "d") (pinfunction "2_d") (pintype "input"))
    )
    (net (code "102") (name "unconnected-(U25-3-Padc)") (class "Default")
      (node (ref "U25") (pin "c") (pinfunction "3_c") (pintype "input"))
    )
  )
)
